# ece411_t2_schematic_6.net
KiCad netlist of a schematic drawn in EAGLE
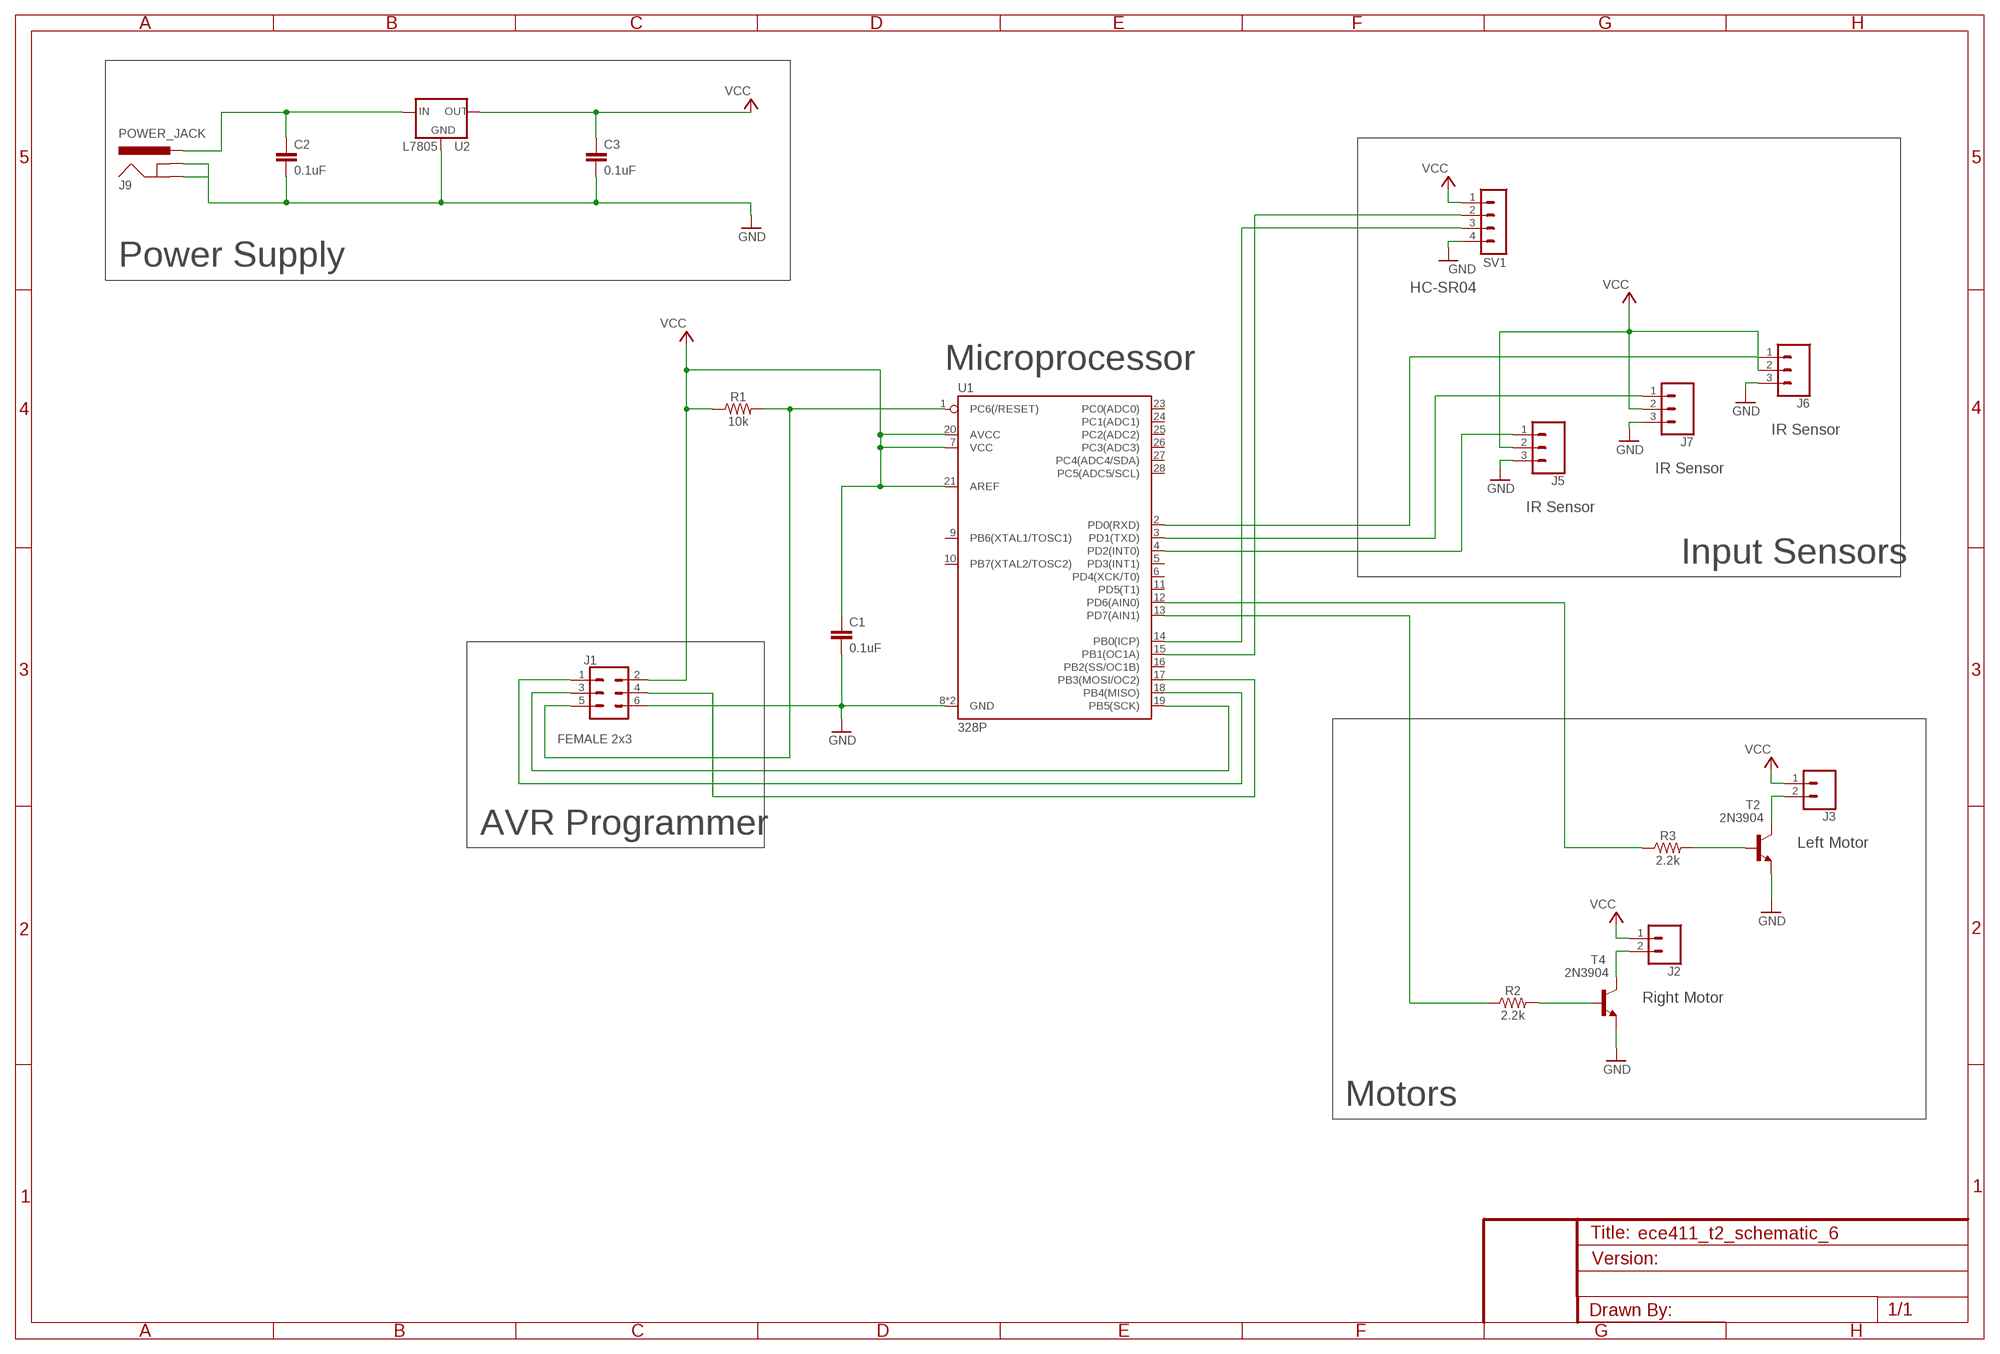
[diagram p0: schematic, sheet 1]

(export (version "E")
  (design (tool "Eeschema 10.0.6"))
  (components
    (comp (ref "C1")
      (value "0.1uF")
      (footprint "eagle-import:0402")
      (libsource (lib "eagle-import") (part "0.1UF-0402-6.3V-10%-X7R"))
    )
    (comp (ref "C2")
      (value "0.1uF")
      (footprint "eagle-import:0402")
      (libsource (lib "eagle-import") (part "0.1UF-0402-6.3V-10%-X7R"))
    )
    (comp (ref "C3")
      (value "0.1uF")
      (footprint "eagle-import:0402")
      (libsource (lib "eagle-import") (part "0.1UF-0402-6.3V-10%-X7R"))
    )
    (comp (ref "J1")
      (value "FEMALE 2x3")
      (footprint "eagle-import:2X3")
      (libsource (lib "eagle-import") (part "CONN_03X2FEMALE"))
    )
    (comp (ref "J2")
      (value "CONN_02")
      (footprint "eagle-import:1X02")
      (libsource (lib "eagle-import") (part "CONN_02"))
    )
    (comp (ref "J3")
      (value "CONN_02")
      (footprint "eagle-import:1X02")
      (libsource (lib "eagle-import") (part "CONN_02"))
    )
    (comp (ref "J5")
      (value "455-1750-1-ND")
      (footprint "eagle-import:1X03")
      (libsource (lib "eagle-import") (part "CONN_03"))
    )
    (comp (ref "J6")
      (value "455-1750-1-ND")
      (footprint "eagle-import:1X03")
      (libsource (lib "eagle-import") (part "CONN_03"))
    )
    (comp (ref "J7")
      (value "455-1750-1-ND")
      (footprint "eagle-import:1X03")
      (libsource (lib "eagle-import") (part "CONN_03"))
    )
    (comp (ref "J9")
      (value "POWER_JACK")
      (footprint "eagle-import:POWER_JACK_PTH")
      (libsource (lib "eagle-import") (part "POWER_JACK"))
    )
    (comp (ref "R1")
      (value "10k")
      (footprint "eagle-import:0402")
      (libsource (lib "eagle-import") (part "10KOHM-0402-1/16W-1%"))
    )
    (comp (ref "R2")
      (value "2.2k")
      (footprint "eagle-import:0603")
      (libsource (lib "eagle-import") (part "2.2KOHM-0603-1/10W-1%"))
    )
    (comp (ref "R3")
      (value "2.2k")
      (footprint "eagle-import:0603")
      (libsource (lib "eagle-import") (part "2.2KOHM-0603-1/10W-1%"))
    )
    (comp (ref "SV1")
      (value "MA04-1")
      (footprint "eagle-import:MA04-1")
      (libsource (lib "eagle-import") (part "MA04-1"))
    )
    (comp (ref "T2")
      (value "2N3904")
      (footprint "eagle-import:TO92")
      (libsource (lib "eagle-import") (part "2N3904"))
    )
    (comp (ref "T4")
      (value "2N3904")
      (footprint "eagle-import:TO92")
      (libsource (lib "eagle-import") (part "2N3904"))
    )
    (comp (ref "U1")
      (value "328P")
      (footprint "eagle-import:DIP28")
      (libsource (lib "eagle-import") (part "ATMEGA328P_PDIP"))
    )
    (comp (ref "U2")
      (value "V_REG_78XX-TO-220")
      (footprint "eagle-import:TO-220-ALT")
      (libsource (lib "eagle-import") (part "V_REG_78XX-TO-220"))
    )
  )
  (nets
    (net (code "1") (name "GND") (class "Default")
      (node (ref "C1") (pin "2") (pinfunction "2_2") (pintype "passive"))
      (node (ref "C2") (pin "2") (pinfunction "2_2") (pintype "passive"))
      (node (ref "C3") (pin "2") (pinfunction "2_2") (pintype "passive"))
      (node (ref "J1") (pin "6") (pinfunction "6_6") (pintype "bidirectional"))
      (node (ref "J5") (pin "3") (pinfunction "3_3") (pintype "passive"))
      (node (ref "J6") (pin "3") (pinfunction "3_3") (pintype "passive"))
      (node (ref "J7") (pin "3") (pinfunction "3_3") (pintype "passive"))
      (node (ref "J9") (pin "GNDBREAK") (pinfunction "GNDBREAK_GNDBREAK") (pintype "bidirectional"))
      (node (ref "SV1") (pin "4") (pinfunction "4_4") (pintype "passive"))
      (node (ref "T2") (pin "3") (pinfunction "E_3") (pintype "passive"))
      (node (ref "T4") (pin "3") (pinfunction "E_3") (pintype "passive"))
      (node (ref "U1") (pin "22") (pinfunction "GND_22") (pintype "bidirectional"))
      (node (ref "U1") (pin "8") (pinfunction "GND_8") (pintype "bidirectional"))
      (node (ref "U2") (pin "GND") (pinfunction "GND_GND") (pintype "input"))
    )
    (net (code "2") (name "Net-(C2-Pad1)") (class "Default")
      (node (ref "C2") (pin "1") (pinfunction "1_1") (pintype "passive"))
      (node (ref "J9") (pin "PWR") (pinfunction "PWR_PWR") (pintype "bidirectional"))
      (node (ref "U2") (pin "IN") (pinfunction "IN_IN") (pintype "input"))
    )
    (net (code "3") (name "Net-(T2-B)") (class "Default")
      (node (ref "R3") (pin "2") (pinfunction "2_2") (pintype "passive"))
      (node (ref "T2") (pin "2") (pinfunction "B_2") (pintype "passive"))
    )
    (net (code "4") (name "Net-(T2-C)") (class "Default")
      (node (ref "J3") (pin "2") (pinfunction "2_2") (pintype "passive"))
      (node (ref "T2") (pin "1") (pinfunction "C_1") (pintype "passive"))
    )
    (net (code "5") (name "Net-(T4-B)") (class "Default")
      (node (ref "R2") (pin "2") (pinfunction "2_2") (pintype "passive"))
      (node (ref "T4") (pin "2") (pinfunction "B_2") (pintype "passive"))
    )
    (net (code "6") (name "Net-(U1-PB0(ICP))") (class "Default")
      (node (ref "SV1") (pin "3") (pinfunction "3_3") (pintype "passive"))
      (node (ref "U1") (pin "14") (pinfunction "PB0(ICP)_14") (pintype "bidirectional"))
    )
    (net (code "7") (name "Net-(U1-PB1(OC1A))") (class "Default")
      (node (ref "SV1") (pin "2") (pinfunction "2_2") (pintype "passive"))
      (node (ref "U1") (pin "15") (pinfunction "PB1(OC1A)_15") (pintype "bidirectional"))
    )
    (net (code "8") (name "Net-(U1-PB3(MOSI{slash}OC2))") (class "Default")
      (node (ref "J1") (pin "4") (pinfunction "4_4") (pintype "bidirectional"))
      (node (ref "U1") (pin "17") (pinfunction "PB3(MOSI/OC2)_17") (pintype "bidirectional"))
    )
    (net (code "9") (name "Net-(U1-PB4(MISO))") (class "Default")
      (node (ref "J1") (pin "1") (pinfunction "1_1") (pintype "bidirectional"))
      (node (ref "U1") (pin "18") (pinfunction "PB4(MISO)_18") (pintype "bidirectional"))
    )
    (net (code "10") (name "Net-(U1-PB5(SCK))") (class "Default")
      (node (ref "J1") (pin "3") (pinfunction "3_3") (pintype "bidirectional"))
      (node (ref "U1") (pin "19") (pinfunction "PB5(SCK)_19") (pintype "bidirectional"))
    )
    (net (code "11") (name "Net-(U1-PC6({slash}RESET))") (class "Default")
      (node (ref "J1") (pin "5") (pinfunction "5_5") (pintype "bidirectional"))
      (node (ref "R1") (pin "2") (pinfunction "2_2") (pintype "passive"))
      (node (ref "U1") (pin "1") (pinfunction "PC6(/RESET)_1") (pintype "bidirectional"))
    )
    (net (code "12") (name "Net-(U1-PD0(RXD))") (class "Default")
      (node (ref "J6") (pin "1") (pinfunction "1_1") (pintype "passive"))
      (node (ref "U1") (pin "2") (pinfunction "PD0(RXD)_2") (pintype "bidirectional"))
    )
    (net (code "13") (name "Net-(U1-PD1(TXD))") (class "Default")
      (node (ref "J7") (pin "1") (pinfunction "1_1") (pintype "passive"))
      (node (ref "U1") (pin "3") (pinfunction "PD1(TXD)_3") (pintype "bidirectional"))
    )
    (net (code "14") (name "Net-(U1-PD2(INT0))") (class "Default")
      (node (ref "J5") (pin "1") (pinfunction "1_1") (pintype "passive"))
      (node (ref "U1") (pin "4") (pinfunction "PD2(INT0)_4") (pintype "bidirectional"))
    )
    (net (code "15") (name "Net-(U1-PD6(AIN0))") (class "Default")
      (node (ref "R3") (pin "1") (pinfunction "1_1") (pintype "passive"))
      (node (ref "U1") (pin "12") (pinfunction "PD6(AIN0)_12") (pintype "bidirectional"))
    )
    (net (code "16") (name "Net-(U1-PD7(AIN1))") (class "Default")
      (node (ref "R2") (pin "1") (pinfunction "1_1") (pintype "passive"))
      (node (ref "U1") (pin "13") (pinfunction "PD7(AIN1)_13") (pintype "bidirectional"))
    )
    (net (code "17") (name "VCC") (class "Default")
      (node (ref "C1") (pin "1") (pinfunction "1_1") (pintype "passive"))
      (node (ref "C3") (pin "1") (pinfunction "1_1") (pintype "passive"))
      (node (ref "J1") (pin "2") (pinfunction "2_2") (pintype "bidirectional"))
      (node (ref "J2") (pin "1") (pinfunction "1_1") (pintype "passive"))
      (node (ref "J2") (pin "2") (pinfunction "2_2") (pintype "passive"))
      (node (ref "J3") (pin "1") (pinfunction "1_1") (pintype "passive"))
      (node (ref "J5") (pin "2") (pinfunction "2_2") (pintype "passive"))
      (node (ref "J6") (pin "2") (pinfunction "2_2") (pintype "passive"))
      (node (ref "J7") (pin "2") (pinfunction "2_2") (pintype "passive"))
      (node (ref "R1") (pin "1") (pinfunction "1_1") (pintype "passive"))
      (node (ref "SV1") (pin "1") (pinfunction "1_1") (pintype "passive"))
      (node (ref "T4") (pin "1") (pinfunction "C_1") (pintype "passive"))
      (node (ref "U1") (pin "20") (pinfunction "AVCC_20") (pintype "bidirectional"))
      (node (ref "U1") (pin "21") (pinfunction "AREF_21") (pintype "bidirectional"))
      (node (ref "U1") (pin "7") (pinfunction "VCC_7") (pintype "bidirectional"))
      (node (ref "U2") (pin "OUT") (pinfunction "OUT_OUT") (pintype "passive"))
    )
    (net (code "18") (name "unconnected-(J9-PadGND)") (class "Default")
      (node (ref "J9") (pin "GND") (pinfunction "GND_GND") (pintype "bidirectional"))
    )
    (net (code "19") (name "unconnected-(U1-PB2(SS{slash}OC1B)-Pad16)") (class "Default")
      (node (ref "U1") (pin "16") (pinfunction "PB2(SS/OC1B)_16") (pintype "bidirectional"))
    )
    (net (code "20") (name "unconnected-(U1-PB6(XTAL1{slash}TOSC1)-Pad9)") (class "Default")
      (node (ref "U1") (pin "9") (pinfunction "PB6(XTAL1/TOSC1)_9") (pintype "bidirectional"))
    )
    (net (code "21") (name "unconnected-(U1-PB7(XTAL2{slash}TOSC2)-Pad10)") (class "Default")
      (node (ref "U1") (pin "10") (pinfunction "PB7(XTAL2/TOSC2)_10") (pintype "bidirectional"))
    )
    (net (code "22") (name "unconnected-(U1-PC0(ADC0)-Pad23)") (class "Default")
      (node (ref "U1") (pin "23") (pinfunction "PC0(ADC0)_23") (pintype "bidirectional"))
    )
    (net (code "23") (name "unconnected-(U1-PC1(ADC1)-Pad24)") (class "Default")
      (node (ref "U1") (pin "24") (pinfunction "PC1(ADC1)_24") (pintype "bidirectional"))
    )
    (net (code "24") (name "unconnected-(U1-PC2(ADC2)-Pad25)") (class "Default")
      (node (ref "U1") (pin "25") (pinfunction "PC2(ADC2)_25") (pintype "bidirectional"))
    )
    (net (code "25") (name "unconnected-(U1-PC3(ADC3)-Pad26)") (class "Default")
      (node (ref "U1") (pin "26") (pinfunction "PC3(ADC3)_26") (pintype "bidirectional"))
    )
    (net (code "26") (name "unconnected-(U1-PC4(ADC4{slash}SDA)-Pad27)") (class "Default")
      (node (ref "U1") (pin "27") (pinfunction "PC4(ADC4/SDA)_27") (pintype "bidirectional"))
    )
    (net (code "27") (name "unconnected-(U1-PC5(ADC5{slash}SCL)-Pad28)") (class "Default")
      (node (ref "U1") (pin "28") (pinfunction "PC5(ADC5/SCL)_28") (pintype "bidirectional"))
    )
    (net (code "28") (name "unconnected-(U1-PD3(INT1)-Pad5)") (class "Default")
      (node (ref "U1") (pin "5") (pinfunction "PD3(INT1)_5") (pintype "bidirectional"))
    )
    (net (code "29") (name "unconnected-(U1-PD4(XCK{slash}T0)-Pad6)") (class "Default")
      (node (ref "U1") (pin "6") (pinfunction "PD4(XCK/T0)_6") (pintype "bidirectional"))
    )
    (net (code "30") (name "unconnected-(U1-PD5(T1)-Pad11)") (class "Default")
      (node (ref "U1") (pin "11") (pinfunction "PD5(T1)_11") (pintype "bidirectional"))
    )
  )
)
